# Shruti_pothole.net
KiCad netlist of a schematic drawn in EAGLE
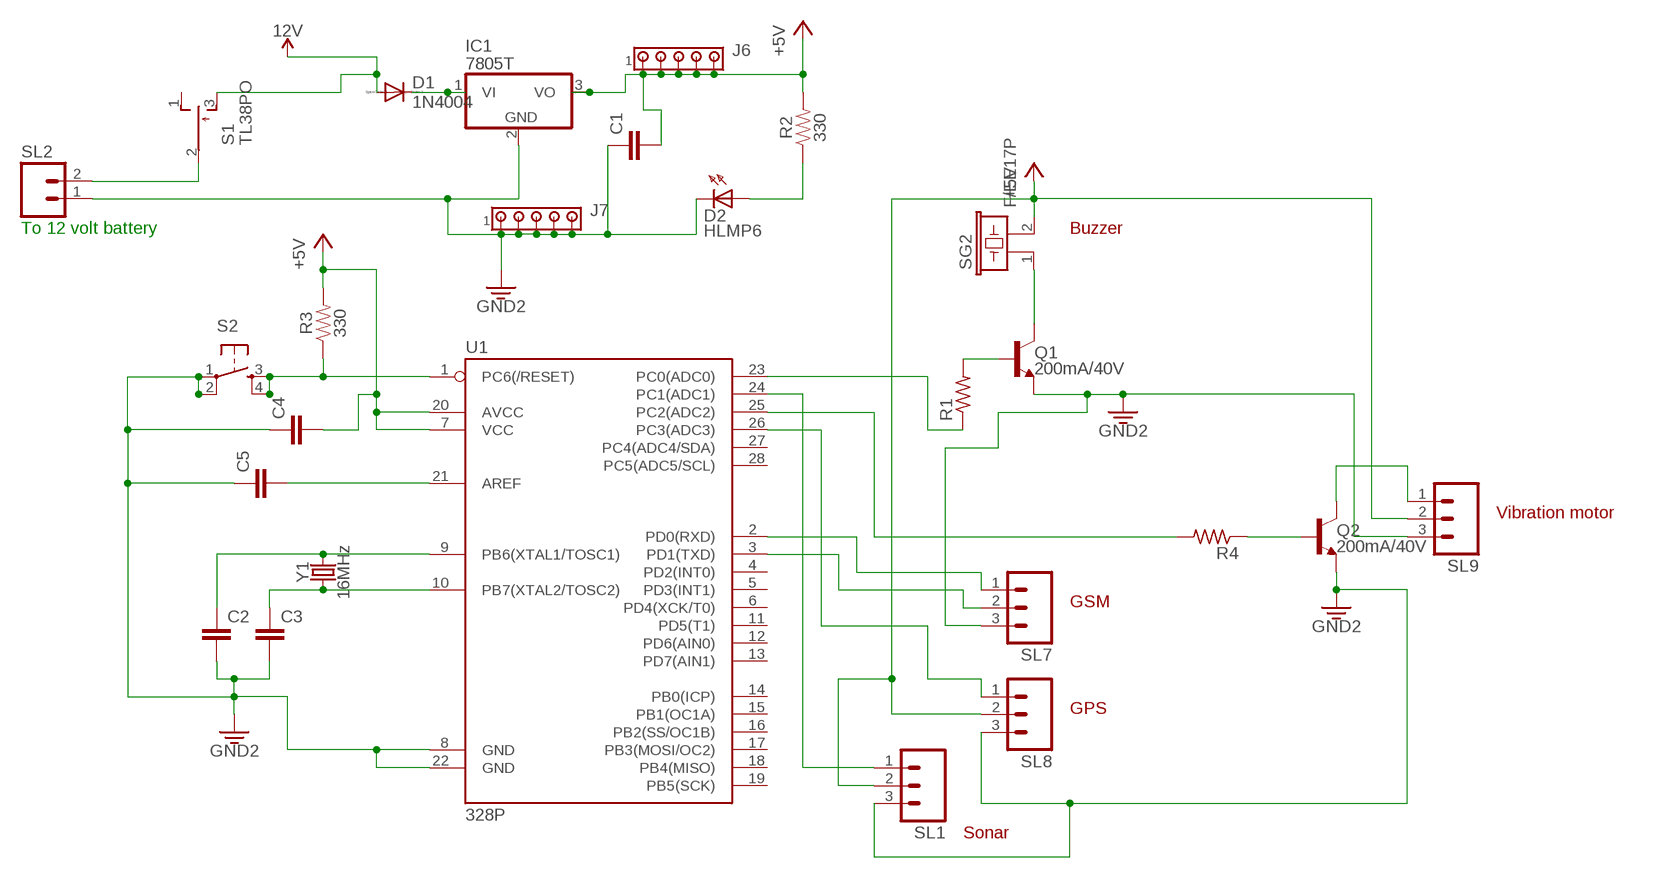
[diagram p0: schematic, sheet 1]

(export (version "E")
  (design (tool "Eeschema 10.0.6"))
  (components
    (comp (ref "C1")
      (value "C5/2.5")
      (footprint "eagle-import:C5B2.5")
      (libsource (lib "eagle-import") (part "C5/2.5"))
    )
    (comp (ref "C2")
      (value "C5/2.5")
      (footprint "eagle-import:C5B2.5")
      (libsource (lib "eagle-import") (part "C5/2.5"))
    )
    (comp (ref "C3")
      (value "C5/2.5")
      (footprint "eagle-import:C5B2.5")
      (libsource (lib "eagle-import") (part "C5/2.5"))
    )
    (comp (ref "C4")
      (value "C5/2.5")
      (footprint "eagle-import:C5B2.5")
      (libsource (lib "eagle-import") (part "C5/2.5"))
    )
    (comp (ref "C5")
      (value "C5/2.5")
      (footprint "eagle-import:C5B2.5")
      (libsource (lib "eagle-import") (part "C5/2.5"))
    )
    (comp (ref "D1")
      (value "1N4004")
      (footprint "eagle-import:DO41-10")
      (libsource (lib "eagle-import") (part "1N4004"))
    )
    (comp (ref "D2")
      (value "HLMP6")
      (footprint "eagle-import:HLMP6")
      (fields (field (name "MF") "AGILENT TECHNOLOGIES") (field (name "MPN") "HLMP-6500"))
      (libsource (lib "eagle-import") (part "HLMP6"))
    )
    (comp (ref "IC1")
      (value "7805T")
      (footprint "eagle-import:TO220H")
      (libsource (lib "eagle-import") (part "78T05"))
    )
    (comp (ref "J6")
      (value "MTA05-100")
      (footprint "eagle-import:10X05MTA")
      (libsource (lib "eagle-import") (part "MTA05-100"))
    )
    (comp (ref "J7")
      (value "MTA05-100")
      (footprint "eagle-import:10X05MTA")
      (libsource (lib "eagle-import") (part "MTA05-100"))
    )
    (comp (ref "Q1")
      (value "200mA/40V")
      (footprint "eagle-import:TO-92")
      (libsource (lib "eagle-import") (part "TRANS_NPN-2N3904"))
    )
    (comp (ref "Q2")
      (value "200mA/40V")
      (footprint "eagle-import:TO-92")
      (libsource (lib "eagle-import") (part "TRANS_NPN-2N3904"))
    )
    (comp (ref "R1")
      (value "R-US_0204/7")
      (footprint "eagle-import:0204_7")
      (libsource (lib "eagle-import") (part "R-US_0204/7"))
    )
    (comp (ref "R2")
      (value "330")
      (footprint "eagle-import:AXIAL-0.3")
      (libsource (lib "eagle-import") (part "330OHM-HORIZ-1/10W-5%"))
    )
    (comp (ref "R3")
      (value "330")
      (footprint "eagle-import:AXIAL-0.3")
      (libsource (lib "eagle-import") (part "330OHM-HORIZ-1/10W-5%"))
    )
    (comp (ref "R4")
      (value "R-US_0204/7")
      (footprint "eagle-import:0204_7")
      (libsource (lib "eagle-import") (part "R-US_0204/7"))
    )
    (comp (ref "S1")
      (value "TL38PO")
      (footprint "eagle-import:TL3XPO")
      (libsource (lib "eagle-import") (part "TL38PO"))
    )
    (comp (ref "S2")
      (value "TAC_SWITCHPTH")
      (footprint "eagle-import:TACTILE-PTH")
      (libsource (lib "eagle-import") (part "TAC_SWITCHPTH"))
    )
    (comp (ref "SG2")
      (value "F/EE17P")
      (footprint "eagle-import:F_EE17P")
      (libsource (lib "eagle-import") (part "F/EE17P"))
    )
    (comp (ref "SL1")
      (value "MA03")
      (footprint "eagle-import:03P")
      (libsource (lib "eagle-import") (part "MA03"))
    )
    (comp (ref "SL2")
      (value "MA02")
      (footprint "eagle-import:02PA")
      (libsource (lib "eagle-import") (part "MA02"))
    )
    (comp (ref "SL7")
      (value "MA03")
      (footprint "eagle-import:03P")
      (libsource (lib "eagle-import") (part "MA03"))
    )
    (comp (ref "SL8")
      (value "MA03")
      (footprint "eagle-import:03P")
      (libsource (lib "eagle-import") (part "MA03"))
    )
    (comp (ref "SL9")
      (value "MA03")
      (footprint "eagle-import:03P")
      (libsource (lib "eagle-import") (part "MA03"))
    )
    (comp (ref "U1")
      (value "328P")
      (footprint "eagle-import:DIP28")
      (libsource (lib "eagle-import") (part "ATMEGA328P_PDIP"))
    )
    (comp (ref "Y1")
      (value "16MHz")
      (footprint "eagle-import:HC49US")
      (libsource (lib "eagle-import") (part "CRYSTAL-16MHZPTH-HC49US"))
    )
  )
  (nets
    (net (code "1") (name "+5V") (class "Default")
      (node (ref "C1") (pin "2") (pinfunction "2_2") (pintype "passive"))
      (node (ref "C4") (pin "2") (pinfunction "2_2") (pintype "passive"))
      (node (ref "IC1") (pin "3") (pinfunction "VO_3") (pintype "passive"))
      (node (ref "J6") (pin "1") (pinfunction "1_1") (pintype "passive"))
      (node (ref "J6") (pin "2") (pinfunction "2_2") (pintype "passive"))
      (node (ref "J6") (pin "3") (pinfunction "3_3") (pintype "passive"))
      (node (ref "J6") (pin "4") (pinfunction "4_4") (pintype "passive"))
      (node (ref "J6") (pin "5") (pinfunction "5_5") (pintype "passive"))
      (node (ref "R2") (pin "P$2") (pinfunction "2_P$2") (pintype "passive"))
      (node (ref "R3") (pin "P$2") (pinfunction "2_P$2") (pintype "passive"))
      (node (ref "SG2") (pin "2") (pinfunction "2_2") (pintype "passive"))
      (node (ref "SL1") (pin "2") (pinfunction "2_2") (pintype "passive"))
      (node (ref "SL8") (pin "2") (pinfunction "2_2") (pintype "passive"))
      (node (ref "SL9") (pin "2") (pinfunction "2_2") (pintype "passive"))
      (node (ref "U1") (pin "20") (pinfunction "AVCC_20") (pintype "bidirectional"))
      (node (ref "U1") (pin "7") (pinfunction "VCC_7") (pintype "bidirectional"))
    )
    (net (code "2") (name "12V") (class "Default")
      (node (ref "D1") (pin "A") (pinfunction "A_A") (pintype "passive"))
      (node (ref "S1") (pin "3") (pinfunction "S_3") (pintype "passive"))
    )
    (net (code "3") (name "GND2") (class "Default")
      (node (ref "C1") (pin "1") (pinfunction "1_1") (pintype "passive"))
      (node (ref "C2") (pin "2") (pinfunction "2_2") (pintype "passive"))
      (node (ref "C3") (pin "2") (pinfunction "2_2") (pintype "passive"))
      (node (ref "C4") (pin "1") (pinfunction "1_1") (pintype "passive"))
      (node (ref "C5") (pin "1") (pinfunction "1_1") (pintype "passive"))
      (node (ref "D2") (pin "K") (pinfunction "K_K") (pintype "passive"))
      (node (ref "IC1") (pin "2") (pinfunction "GND_2") (pintype "passive"))
      (node (ref "J7") (pin "1") (pinfunction "1_1") (pintype "passive"))
      (node (ref "J7") (pin "2") (pinfunction "2_2") (pintype "passive"))
      (node (ref "J7") (pin "3") (pinfunction "3_3") (pintype "passive"))
      (node (ref "J7") (pin "4") (pinfunction "4_4") (pintype "passive"))
      (node (ref "J7") (pin "5") (pinfunction "5_5") (pintype "passive"))
      (node (ref "Q1") (pin "1") (pinfunction "E_1") (pintype "passive"))
      (node (ref "Q2") (pin "1") (pinfunction "E_1") (pintype "passive"))
      (node (ref "S2") (pin "1") (pinfunction "1_1") (pintype "passive"))
      (node (ref "S2") (pin "2") (pinfunction "2_2") (pintype "passive"))
      (node (ref "SL1") (pin "3") (pinfunction "3_3") (pintype "passive"))
      (node (ref "SL2") (pin "1") (pinfunction "1_1") (pintype "passive"))
      (node (ref "SL7") (pin "3") (pinfunction "3_3") (pintype "passive"))
      (node (ref "SL8") (pin "3") (pinfunction "3_3") (pintype "passive"))
      (node (ref "SL9") (pin "3") (pinfunction "3_3") (pintype "passive"))
      (node (ref "U1") (pin "22") (pinfunction "GND_22") (pintype "bidirectional"))
      (node (ref "U1") (pin "8") (pinfunction "GND_8") (pintype "bidirectional"))
    )
    (net (code "4") (name "Net-(IC1-VI)") (class "Default")
      (node (ref "D1") (pin "C") (pinfunction "C_C") (pintype "passive"))
      (node (ref "IC1") (pin "1") (pinfunction "VI_1") (pintype "input"))
    )
    (net (code "5") (name "Net-(Q1-B)") (class "Default")
      (node (ref "Q1") (pin "2") (pinfunction "B_2") (pintype "passive"))
      (node (ref "R1") (pin "2") (pinfunction "2_2") (pintype "passive"))
    )
    (net (code "6") (name "Net-(Q1-C)") (class "Default")
      (node (ref "Q1") (pin "3") (pinfunction "C_3") (pintype "passive"))
      (node (ref "SG2") (pin "1") (pinfunction "1_1") (pintype "passive"))
    )
    (net (code "7") (name "Net-(Q2-B)") (class "Default")
      (node (ref "Q2") (pin "2") (pinfunction "B_2") (pintype "passive"))
      (node (ref "R4") (pin "1") (pinfunction "1_1") (pintype "passive"))
    )
    (net (code "8") (name "Net-(Q2-C)") (class "Default")
      (node (ref "Q2") (pin "3") (pinfunction "C_3") (pintype "passive"))
      (node (ref "SL9") (pin "1") (pinfunction "1_1") (pintype "passive"))
    )
    (net (code "9") (name "Net-(R2-1)") (class "Default")
      (node (ref "D2") (pin "A") (pinfunction "A_A") (pintype "passive"))
      (node (ref "R2") (pin "P$1") (pinfunction "1_P$1") (pintype "passive"))
    )
    (net (code "10") (name "Net-(R3-1)") (class "Default")
      (node (ref "R3") (pin "P$1") (pinfunction "1_P$1") (pintype "passive"))
      (node (ref "S2") (pin "3") (pinfunction "3_3") (pintype "passive"))
      (node (ref "S2") (pin "4") (pinfunction "4_4") (pintype "passive"))
      (node (ref "U1") (pin "1") (pinfunction "PC6(/RESET)_1") (pintype "bidirectional"))
    )
    (net (code "11") (name "Net-(S1-P)") (class "Default")
      (node (ref "S1") (pin "2") (pinfunction "P_2") (pintype "passive"))
      (node (ref "SL2") (pin "2") (pinfunction "2_2") (pintype "passive"))
    )
    (net (code "12") (name "Net-(U1-AREF)") (class "Default")
      (node (ref "C5") (pin "2") (pinfunction "2_2") (pintype "passive"))
      (node (ref "U1") (pin "21") (pinfunction "AREF_21") (pintype "bidirectional"))
    )
    (net (code "13") (name "Net-(U1-PB6(XTAL1{slash}TOSC1))") (class "Default")
      (node (ref "C2") (pin "1") (pinfunction "1_1") (pintype "passive"))
      (node (ref "U1") (pin "9") (pinfunction "PB6(XTAL1/TOSC1)_9") (pintype "bidirectional"))
      (node (ref "Y1") (pin "2") (pinfunction "2_2") (pintype "passive"))
    )
    (net (code "14") (name "Net-(U1-PB7(XTAL2{slash}TOSC2))") (class "Default")
      (node (ref "C3") (pin "1") (pinfunction "1_1") (pintype "passive"))
      (node (ref "U1") (pin "10") (pinfunction "PB7(XTAL2/TOSC2)_10") (pintype "bidirectional"))
      (node (ref "Y1") (pin "1") (pinfunction "1_1") (pintype "passive"))
    )
    (net (code "15") (name "Net-(U1-PC0(ADC0))") (class "Default")
      (node (ref "R1") (pin "1") (pinfunction "1_1") (pintype "passive"))
      (node (ref "U1") (pin "23") (pinfunction "PC0(ADC0)_23") (pintype "bidirectional"))
    )
    (net (code "16") (name "Net-(U1-PC1(ADC1))") (class "Default")
      (node (ref "SL1") (pin "1") (pinfunction "1_1") (pintype "passive"))
      (node (ref "U1") (pin "24") (pinfunction "PC1(ADC1)_24") (pintype "bidirectional"))
    )
    (net (code "17") (name "Net-(U1-PC2(ADC2))") (class "Default")
      (node (ref "R4") (pin "2") (pinfunction "2_2") (pintype "passive"))
      (node (ref "U1") (pin "25") (pinfunction "PC2(ADC2)_25") (pintype "bidirectional"))
    )
    (net (code "18") (name "Net-(U1-PC3(ADC3))") (class "Default")
      (node (ref "SL8") (pin "1") (pinfunction "1_1") (pintype "passive"))
      (node (ref "U1") (pin "26") (pinfunction "PC3(ADC3)_26") (pintype "bidirectional"))
    )
    (net (code "19") (name "Net-(U1-PD0(RXD))") (class "Default")
      (node (ref "SL7") (pin "1") (pinfunction "1_1") (pintype "passive"))
      (node (ref "U1") (pin "2") (pinfunction "PD0(RXD)_2") (pintype "bidirectional"))
    )
    (net (code "20") (name "Net-(U1-PD1(TXD))") (class "Default")
      (node (ref "SL7") (pin "2") (pinfunction "2_2") (pintype "passive"))
      (node (ref "U1") (pin "3") (pinfunction "PD1(TXD)_3") (pintype "bidirectional"))
    )
    (net (code "21") (name "unconnected-(S1-O-Pad1)") (class "Default")
      (node (ref "S1") (pin "1") (pinfunction "O_1") (pintype "passive"))
    )
    (net (code "22") (name "unconnected-(U1-PB0(ICP)-Pad14)") (class "Default")
      (node (ref "U1") (pin "14") (pinfunction "PB0(ICP)_14") (pintype "bidirectional"))
    )
    (net (code "23") (name "unconnected-(U1-PB1(OC1A)-Pad15)") (class "Default")
      (node (ref "U1") (pin "15") (pinfunction "PB1(OC1A)_15") (pintype "bidirectional"))
    )
    (net (code "24") (name "unconnected-(U1-PB2(SS{slash}OC1B)-Pad16)") (class "Default")
      (node (ref "U1") (pin "16") (pinfunction "PB2(SS/OC1B)_16") (pintype "bidirectional"))
    )
    (net (code "25") (name "unconnected-(U1-PB3(MOSI{slash}OC2)-Pad17)") (class "Default")
      (node (ref "U1") (pin "17") (pinfunction "PB3(MOSI/OC2)_17") (pintype "bidirectional"))
    )
    (net (code "26") (name "unconnected-(U1-PB4(MISO)-Pad18)") (class "Default")
      (node (ref "U1") (pin "18") (pinfunction "PB4(MISO)_18") (pintype "bidirectional"))
    )
    (net (code "27") (name "unconnected-(U1-PB5(SCK)-Pad19)") (class "Default")
      (node (ref "U1") (pin "19") (pinfunction "PB5(SCK)_19") (pintype "bidirectional"))
    )
    (net (code "28") (name "unconnected-(U1-PC4(ADC4{slash}SDA)-Pad27)") (class "Default")
      (node (ref "U1") (pin "27") (pinfunction "PC4(ADC4/SDA)_27") (pintype "bidirectional"))
    )
    (net (code "29") (name "unconnected-(U1-PC5(ADC5{slash}SCL)-Pad28)") (class "Default")
      (node (ref "U1") (pin "28") (pinfunction "PC5(ADC5/SCL)_28") (pintype "bidirectional"))
    )
    (net (code "30") (name "unconnected-(U1-PD2(INT0)-Pad4)") (class "Default")
      (node (ref "U1") (pin "4") (pinfunction "PD2(INT0)_4") (pintype "bidirectional"))
    )
    (net (code "31") (name "unconnected-(U1-PD3(INT1)-Pad5)") (class "Default")
      (node (ref "U1") (pin "5") (pinfunction "PD3(INT1)_5") (pintype "bidirectional"))
    )
    (net (code "32") (name "unconnected-(U1-PD4(XCK{slash}T0)-Pad6)") (class "Default")
      (node (ref "U1") (pin "6") (pinfunction "PD4(XCK/T0)_6") (pintype "bidirectional"))
    )
    (net (code "33") (name "unconnected-(U1-PD5(T1)-Pad11)") (class "Default")
      (node (ref "U1") (pin "11") (pinfunction "PD5(T1)_11") (pintype "bidirectional"))
    )
    (net (code "34") (name "unconnected-(U1-PD6(AIN0)-Pad12)") (class "Default")
      (node (ref "U1") (pin "12") (pinfunction "PD6(AIN0)_12") (pintype "bidirectional"))
    )
    (net (code "35") (name "unconnected-(U1-PD7(AIN1)-Pad13)") (class "Default")
      (node (ref "U1") (pin "13") (pinfunction "PD7(AIN1)_13") (pintype "bidirectional"))
    )
  )
)
